# main.net
KiCad netlist of a schematic drawn in EAGLE
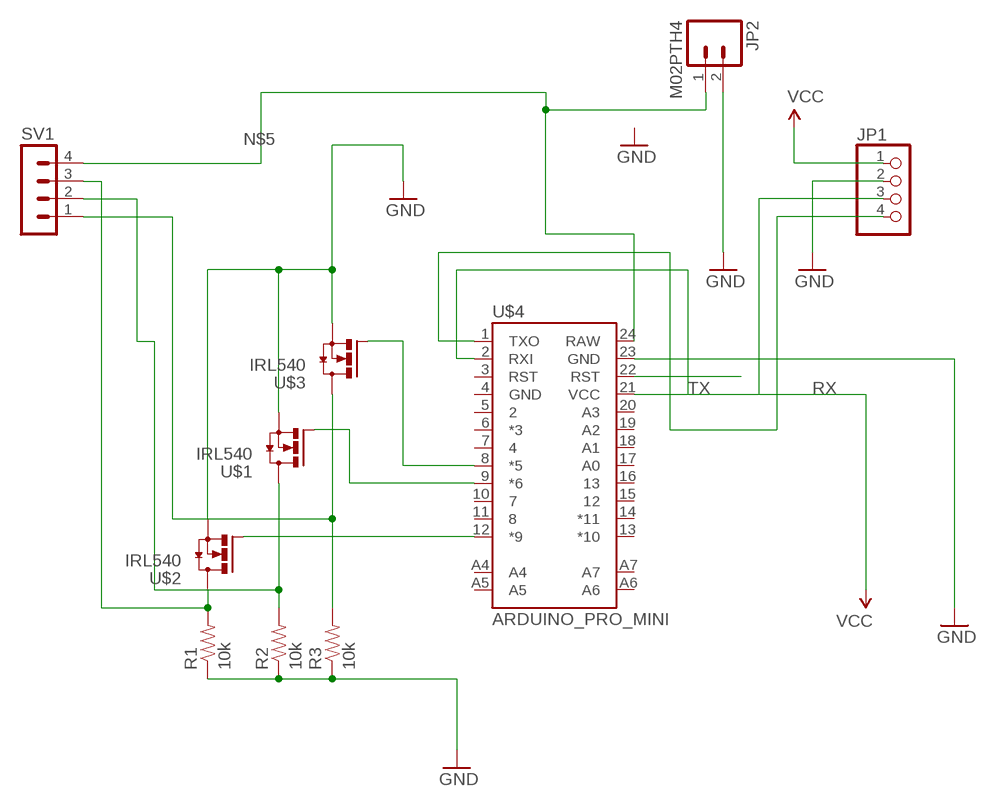
[diagram p0: schematic, sheet 1]

(export (version "E")
  (design (tool "Eeschema 10.0.6"))
  (components
    (comp (ref "JP1")
      (value "PINHD-1X4")
      (footprint "eagle-import:1X04")
      (libsource (lib "eagle-import") (part "PINHD-1X4"))
    )
    (comp (ref "JP2")
      (value "M02PTH4")
      (footprint "eagle-import:1X02_XTRA_BIG")
      (libsource (lib "eagle-import") (part "M02PTH4"))
    )
    (comp (ref "R1")
      (value "10k")
      (footprint "eagle-import:AXIAL-0.4")
      (libsource (lib "eagle-import") (part "RESISTORPTH-1/4W"))
    )
    (comp (ref "R2")
      (value "10k")
      (footprint "eagle-import:AXIAL-0.4")
      (libsource (lib "eagle-import") (part "RESISTORPTH-1/4W"))
    )
    (comp (ref "R3")
      (value "10k")
      (footprint "eagle-import:AXIAL-0.4")
      (libsource (lib "eagle-import") (part "RESISTORPTH-1/4W"))
    )
    (comp (ref "SV1")
      (value "MA04-1")
      (footprint "eagle-import:MA04-1")
      (libsource (lib "eagle-import") (part "MA04-1"))
    )
    (comp (ref "U$1")
      (value "IRL540")
      (footprint "eagle-import:TO220AH")
      (libsource (lib "eagle-import") (part "IRL540"))
    )
    (comp (ref "U$2")
      (value "IRL540")
      (footprint "eagle-import:TO220AH")
      (libsource (lib "eagle-import") (part "IRL540"))
    )
    (comp (ref "U$3")
      (value "IRL540")
      (footprint "eagle-import:TO220AH")
      (libsource (lib "eagle-import") (part "IRL540"))
    )
    (comp (ref "U$4")
      (value "ARDUINO_PRO_MINI")
      (footprint "eagle-import:ARDUINO_PRO_MINI")
      (libsource (lib "eagle-import") (part "ARDUINO_PRO_MINI"))
    )
  )
  (nets
    (net (code "1") (name "/N$5") (class "Default")
      (node (ref "JP2") (pin "1") (pinfunction "1_1") (pintype "passive"))
      (node (ref "SV1") (pin "4") (pinfunction "4_4") (pintype "passive"))
      (node (ref "U$4") (pin "24") (pinfunction "RAW_24") (pintype "bidirectional"))
    )
    (net (code "2") (name "/RX") (class "Default")
      (node (ref "JP1") (pin "4") (pinfunction "4_4") (pintype "passive"))
      (node (ref "U$4") (pin "1") (pinfunction "TXO_1") (pintype "bidirectional"))
    )
    (net (code "3") (name "/TX") (class "Default")
      (node (ref "JP1") (pin "3") (pinfunction "3_3") (pintype "passive"))
      (node (ref "U$4") (pin "2") (pinfunction "RXI_2") (pintype "bidirectional"))
    )
    (net (code "4") (name "GND") (class "Default")
      (node (ref "JP1") (pin "2") (pinfunction "2_2") (pintype "passive"))
      (node (ref "JP2") (pin "2") (pinfunction "2_2") (pintype "passive"))
      (node (ref "R1") (pin "P$1") (pinfunction "1_P$1") (pintype "passive"))
      (node (ref "R2") (pin "P$1") (pinfunction "1_P$1") (pintype "passive"))
      (node (ref "R3") (pin "P$1") (pinfunction "1_P$1") (pintype "passive"))
      (node (ref "U$1") (pin "E") (pinfunction "S_E") (pintype "passive"))
      (node (ref "U$2") (pin "E") (pinfunction "S_E") (pintype "passive"))
      (node (ref "U$3") (pin "E") (pinfunction "S_E") (pintype "passive"))
      (node (ref "U$4") (pin "23") (pinfunction "GND_23") (pintype "bidirectional"))
    )
    (net (code "5") (name "Net-(R1-2)") (class "Default")
      (node (ref "R1") (pin "P$2") (pinfunction "2_P$2") (pintype "passive"))
      (node (ref "SV1") (pin "3") (pinfunction "3_3") (pintype "passive"))
      (node (ref "U$2") (pin "C") (pinfunction "D_C") (pintype "passive"))
    )
    (net (code "6") (name "Net-(R2-2)") (class "Default")
      (node (ref "R2") (pin "P$2") (pinfunction "2_P$2") (pintype "passive"))
      (node (ref "SV1") (pin "2") (pinfunction "2_2") (pintype "passive"))
      (node (ref "U$1") (pin "C") (pinfunction "D_C") (pintype "passive"))
    )
    (net (code "7") (name "Net-(R3-2)") (class "Default")
      (node (ref "R3") (pin "P$2") (pinfunction "2_P$2") (pintype "passive"))
      (node (ref "SV1") (pin "1") (pinfunction "1_1") (pintype "passive"))
      (node (ref "U$3") (pin "C") (pinfunction "D_C") (pintype "passive"))
    )
    (net (code "8") (name "Net-(U$1-G)") (class "Default")
      (node (ref "U$1") (pin "B") (pinfunction "G_B") (pintype "passive"))
      (node (ref "U$4") (pin "9") (pinfunction "*6_9") (pintype "bidirectional"))
    )
    (net (code "9") (name "Net-(U$2-G)") (class "Default")
      (node (ref "U$2") (pin "B") (pinfunction "G_B") (pintype "passive"))
      (node (ref "U$4") (pin "12") (pinfunction "*9_12") (pintype "bidirectional"))
    )
    (net (code "10") (name "Net-(U$3-G)") (class "Default")
      (node (ref "U$3") (pin "B") (pinfunction "G_B") (pintype "passive"))
      (node (ref "U$4") (pin "8") (pinfunction "*5_8") (pintype "bidirectional"))
    )
    (net (code "11") (name "VCC") (class "Default")
      (node (ref "JP1") (pin "1") (pinfunction "1_1") (pintype "passive"))
      (node (ref "U$4") (pin "21") (pinfunction "VCC_21") (pintype "bidirectional"))
    )
    (net (code "12") (name "unconnected-(U$4-*3-Pad6)") (class "Default")
      (node (ref "U$4") (pin "6") (pinfunction "*3_6") (pintype "bidirectional"))
    )
    (net (code "13") (name "unconnected-(U$4-*10-Pad13)") (class "Default")
      (node (ref "U$4") (pin "13") (pinfunction "*10_13") (pintype "bidirectional"))
    )
    (net (code "14") (name "unconnected-(U$4-*11-Pad14)") (class "Default")
      (node (ref "U$4") (pin "14") (pinfunction "*11_14") (pintype "bidirectional"))
    )
    (net (code "15") (name "unconnected-(U$4-2-Pad5)") (class "Default")
      (node (ref "U$4") (pin "5") (pinfunction "2_5") (pintype "bidirectional"))
    )
    (net (code "16") (name "unconnected-(U$4-4-Pad7)") (class "Default")
      (node (ref "U$4") (pin "7") (pinfunction "4_7") (pintype "bidirectional"))
    )
    (net (code "17") (name "unconnected-(U$4-7-Pad10)") (class "Default")
      (node (ref "U$4") (pin "10") (pinfunction "7_10") (pintype "bidirectional"))
    )
    (net (code "18") (name "unconnected-(U$4-8-Pad11)") (class "Default")
      (node (ref "U$4") (pin "11") (pinfunction "8_11") (pintype "bidirectional"))
    )
    (net (code "19") (name "unconnected-(U$4-12-Pad15)") (class "Default")
      (node (ref "U$4") (pin "15") (pinfunction "12_15") (pintype "bidirectional"))
    )
    (net (code "20") (name "unconnected-(U$4-13-Pad16)") (class "Default")
      (node (ref "U$4") (pin "16") (pinfunction "13_16") (pintype "bidirectional"))
    )
    (net (code "21") (name "unconnected-(U$4-A0-Pad17)") (class "Default")
      (node (ref "U$4") (pin "17") (pinfunction "A0_17") (pintype "bidirectional"))
    )
    (net (code "22") (name "unconnected-(U$4-A1-Pad18)") (class "Default")
      (node (ref "U$4") (pin "18") (pinfunction "A1_18") (pintype "bidirectional"))
    )
    (net (code "23") (name "unconnected-(U$4-A2-Pad19)") (class "Default")
      (node (ref "U$4") (pin "19") (pinfunction "A2_19") (pintype "bidirectional"))
    )
    (net (code "24") (name "unconnected-(U$4-A3-Pad20)") (class "Default")
      (node (ref "U$4") (pin "20") (pinfunction "A3_20") (pintype "bidirectional"))
    )
    (net (code "25") (name "unconnected-(U$4-GND-Pad4)") (class "Default")
      (node (ref "U$4") (pin "4") (pinfunction "GND_4") (pintype "bidirectional"))
    )
    (net (code "26") (name "unconnected-(U$4-PadA4)") (class "Default")
      (node (ref "U$4") (pin "A4") (pinfunction "A4_A4") (pintype "bidirectional"))
    )
    (net (code "27") (name "unconnected-(U$4-PadA5)") (class "Default")
      (node (ref "U$4") (pin "A5") (pinfunction "A5_A5") (pintype "bidirectional"))
    )
    (net (code "28") (name "unconnected-(U$4-PadA6)") (class "Default")
      (node (ref "U$4") (pin "A6") (pinfunction "A6_A6") (pintype "bidirectional"))
    )
    (net (code "29") (name "unconnected-(U$4-PadA7)") (class "Default")
      (node (ref "U$4") (pin "A7") (pinfunction "A7_A7") (pintype "bidirectional"))
    )
    (net (code "30") (name "unconnected-(U$4-RST-Pad3)") (class "Default")
      (node (ref "U$4") (pin "3") (pinfunction "RST_3") (pintype "bidirectional"))
    )
    (net (code "31") (name "unconnected-(U$4-RST-Pad22)") (class "Default")
      (node (ref "U$4") (pin "22") (pinfunction "RST_22") (pintype "bidirectional"))
    )
  )
)
